# AudioIN.net
KiCad netlist of a schematic drawn in Altium Designer
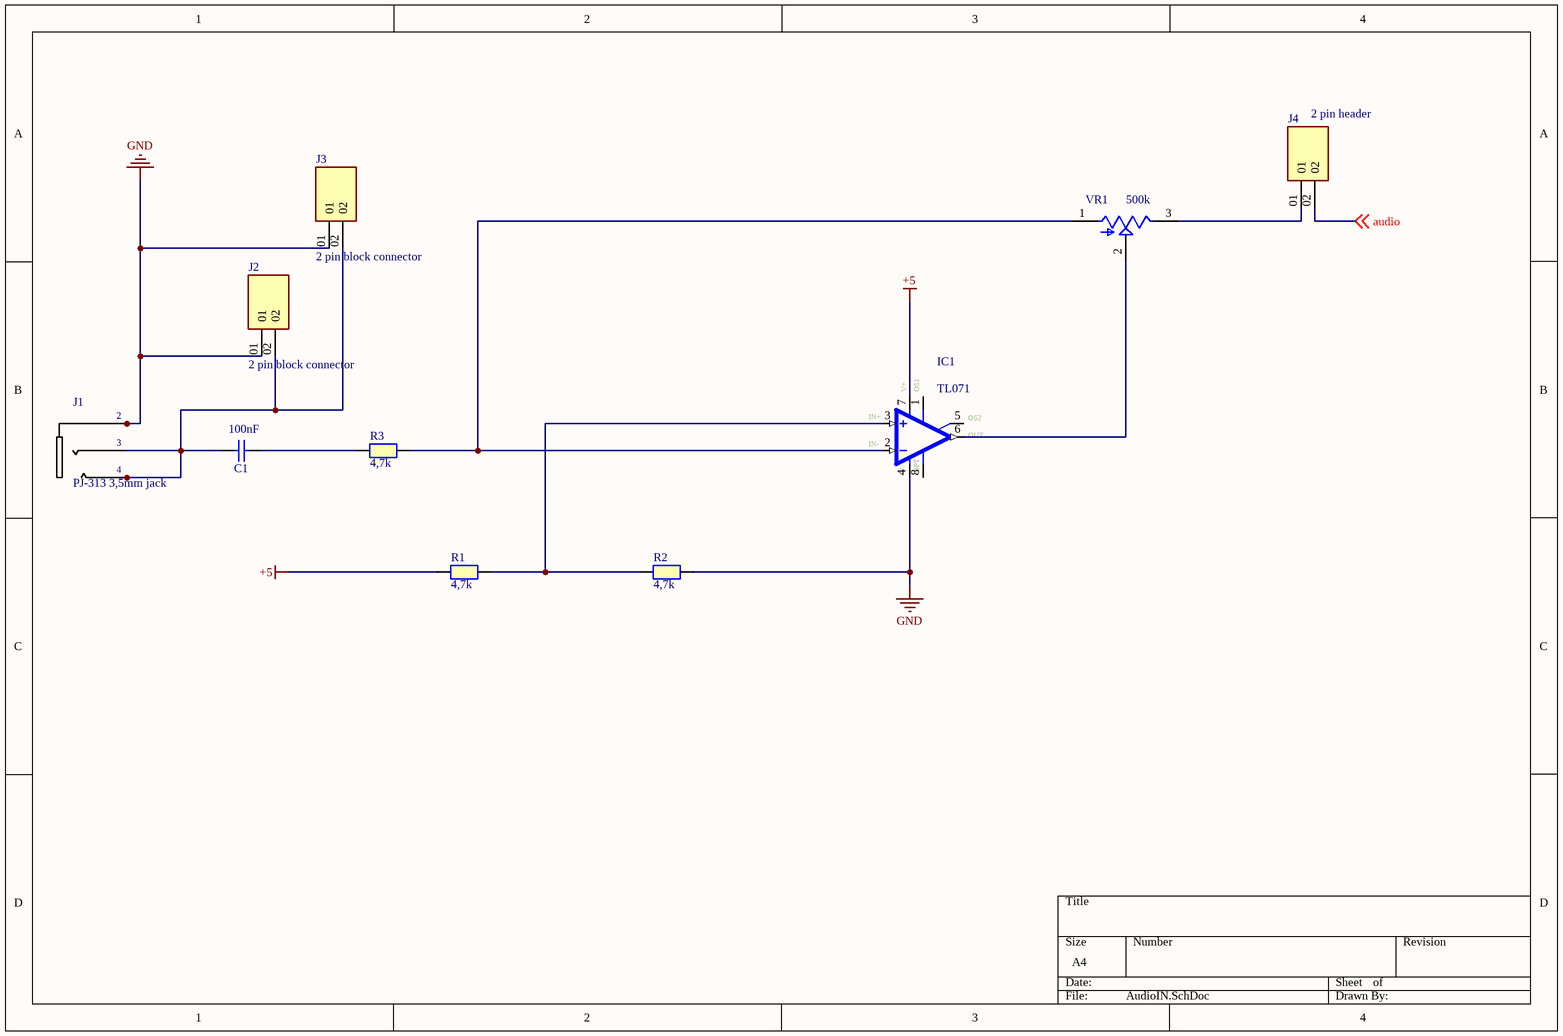
[diagram p0: AudioIN.SchDoc]

(export (version "E")
  (design (tool "Eeschema 10.0.6"))
  (components
    (comp (ref "C1")
      (value "100nF")
      (footprint "CAPC2012X65N")
      (description "100nF Keramic cap")
      (fields
        (field (name "MANUFACTURER PART NUMBER") "885012004008")
        (field (name "MANUFACTURER") "Wurth Elektronik")
      )
      (libsource (lib "SpectrumComponents") (part "885012004008"))
    )
    (comp (ref "IC1")
      (value "TL071")
      (footprint "SpectrumComponents:DIL08")
      (description "J-FET Amplifier 1 Circuit 8-SO")
      (fields (field (name "MF") "STMicroelectronics"))
      (libsource (lib "SpectrumComponents") (part "TL071"))
    )
    (comp (ref "J1")
      (value "PJ-313 3,5mm jack")
      (footprint "*PJ-313_PJ-313(Primary)")
      (description "3,5cm jack")
      (fields (field (name "MP") "PJ313") (field (name "MF") "ADC Telecommunications"))
      (libsource (lib "SpectrumComponents") (part "PJ-313"))
    )
    (comp (ref "J2")
      (value "2 pin block connector")
      (footprint "691210910002")
      (fields (field (name "MP") "HTSW10207TMS") (field (name "MF") "Samtec"))
      (libsource (lib "SpectrumComponents") (part "2 pin header"))
    )
    (comp (ref "J3")
      (value "2 pin block connector")
      (footprint "691210910002")
      (fields (field (name "MP") "HTSW10207TMS") (field (name "MF") "Samtec"))
      (libsource (lib "SpectrumComponents") (part "2 pin header"))
    )
    (comp (ref "J4")
      (value "2 pin header")
      (footprint "SpectrumComponents:SAMTEC_HTSW-102-07-TM-S")
      (description "2 pin header Jumper")
      (fields (field (name "MP") "HTSW10207TMS") (field (name "MF") "Samtec"))
      (libsource (lib "SpectrumComponents") (part "2 pin header"))
    )
    (comp (ref "R1")
      (value "4,7k")
      (footprint "RESC2012X50N")
      (description "4,7k Resistor 0805")
      (fields (field (name "PART NUMBER") "TNPW080510K0BETA") (field (name "MANUFACTURER") "Vishay Dale"))
      (libsource (lib "SpectrumComponents") (part "RESISTOR 0805"))
    )
    (comp (ref "R2")
      (value "4,7k")
      (footprint "RESC2012X50N")
      (description "4,7k Resistor 0805")
      (fields (field (name "PART NUMBER") "TNPW080510K0BETA") (field (name "MANUFACTURER") "Vishay Dale"))
      (libsource (lib "SpectrumComponents") (part "RESISTOR 0805"))
    )
    (comp (ref "R3")
      (value "4,7k")
      (footprint "RESC2012X50N")
      (description "4,7k Resistor 0805")
      (fields (field (name "PART NUMBER") "TNPW080510K0BETA") (field (name "MANUFACTURER") "Vishay Dale"))
      (libsource (lib "SpectrumComponents") (part "RESISTOR 0805"))
    )
    (comp (ref "VR1")
      (value "500k")
      (footprint "TRIM_3362P-1-253LF")
      (description "25 kOhms 0.5W, 1/2W PC Pins Through Hole Trimmer Potentiometer Cermet 1 Turn Top Adjustment")
      (fields (field (name "MF") "Bourns") (field (name "MP") "3362P-1-253LF"))
      (libsource (lib "SpectrumComponents") (part "3362P-1-253LF"))
    )
  )
  (nets
    (net (code "1") (name "+5") (class "Default")
      (node (ref "IC1") (pin "7") (pinfunction "V+_7") (pintype "power_in"))
      (node (ref "R1") (pin "1") (pinfunction "1_1") (pintype "passive"))
    )
    (net (code "2") (name "GND") (class "Default")
      (node (ref "IC1") (pin "4") (pinfunction "V-_4") (pintype "power_in"))
      (node (ref "J1") (pin "2_1") (pinfunction "2_2_1") (pintype "passive"))
      (node (ref "J1") (pin "2_2") (pinfunction "2_2_2") (pintype "passive"))
      (node (ref "J2") (pin "01") (pinfunction "01_01") (pintype "passive"))
      (node (ref "J3") (pin "01") (pinfunction "01_01") (pintype "passive"))
      (node (ref "R2") (pin "2") (pinfunction "2_2") (pintype "passive"))
    )
    (net (code "3") (name "Net-(C1-Pad1)") (class "Default")
      (node (ref "C1") (pin "1") (pinfunction "1_1") (pintype "passive"))
      (node (ref "J1") (pin "3") (pinfunction "3_3") (pintype "passive"))
      (node (ref "J1") (pin "4_1") (pinfunction "4_4_1") (pintype "passive"))
      (node (ref "J1") (pin "4_2") (pinfunction "4_4_2") (pintype "passive"))
      (node (ref "J2") (pin "02") (pinfunction "02_02") (pintype "passive"))
      (node (ref "J3") (pin "02") (pinfunction "02_02") (pintype "passive"))
    )
    (net (code "4") (name "Net-(C1-Pad2)") (class "Default")
      (node (ref "C1") (pin "2") (pinfunction "2_2") (pintype "passive"))
      (node (ref "R3") (pin "1") (pinfunction "1_1") (pintype "passive"))
    )
    (net (code "5") (name "Net-(IC1-+IN)") (class "Default")
      (node (ref "IC1") (pin "3") (pinfunction "+IN_3") (pintype "input"))
      (node (ref "R1") (pin "2") (pinfunction "2_2") (pintype "passive"))
      (node (ref "R2") (pin "1") (pinfunction "1_1") (pintype "passive"))
    )
    (net (code "6") (name "Net-(IC1--IN)") (class "Default")
      (node (ref "IC1") (pin "2") (pinfunction "-IN_2") (pintype "input"))
      (node (ref "R3") (pin "2") (pinfunction "2_2") (pintype "passive"))
      (node (ref "VR1") (pin "1") (pinfunction "CCW_1") (pintype "passive"))
    )
    (net (code "7") (name "Net-(IC1-OUT)") (class "Default")
      (node (ref "IC1") (pin "6") (pinfunction "OUT_6") (pintype "output"))
      (node (ref "VR1") (pin "2") (pinfunction "WIPER_2") (pintype "passive"))
    )
    (net (code "8") (name "Net-(VR1-CW)") (class "Default")
      (node (ref "J4") (pin "01") (pinfunction "01_01") (pintype "passive"))
      (node (ref "VR1") (pin "3") (pinfunction "CW_3") (pintype "passive"))
    )
    (net (code "9") (name "audio") (class "Default")
      (node (ref "J4") (pin "02") (pinfunction "02_02") (pintype "passive"))
    )
    (net (code "10") (name "unconnected-(IC1-ON1-Pad1)") (class "Default")
      (node (ref "IC1") (pin "1") (pinfunction "ON1_1") (pintype "passive"))
    )
    (net (code "11") (name "unconnected-(IC1-ON2-Pad5)") (class "Default")
      (node (ref "IC1") (pin "5") (pinfunction "ON2_5") (pintype "passive"))
    )
    (net (code "12") (name "unconnected-(IC1-OPT-Pad8)") (class "Default")
      (node (ref "IC1") (pin "8") (pinfunction "OPT_8") (pintype "passive"))
    )
  )
)
